# 2025_08_25_usb2spi.net
KiCad netlist of a schematic drawn in EasyEDA Pro
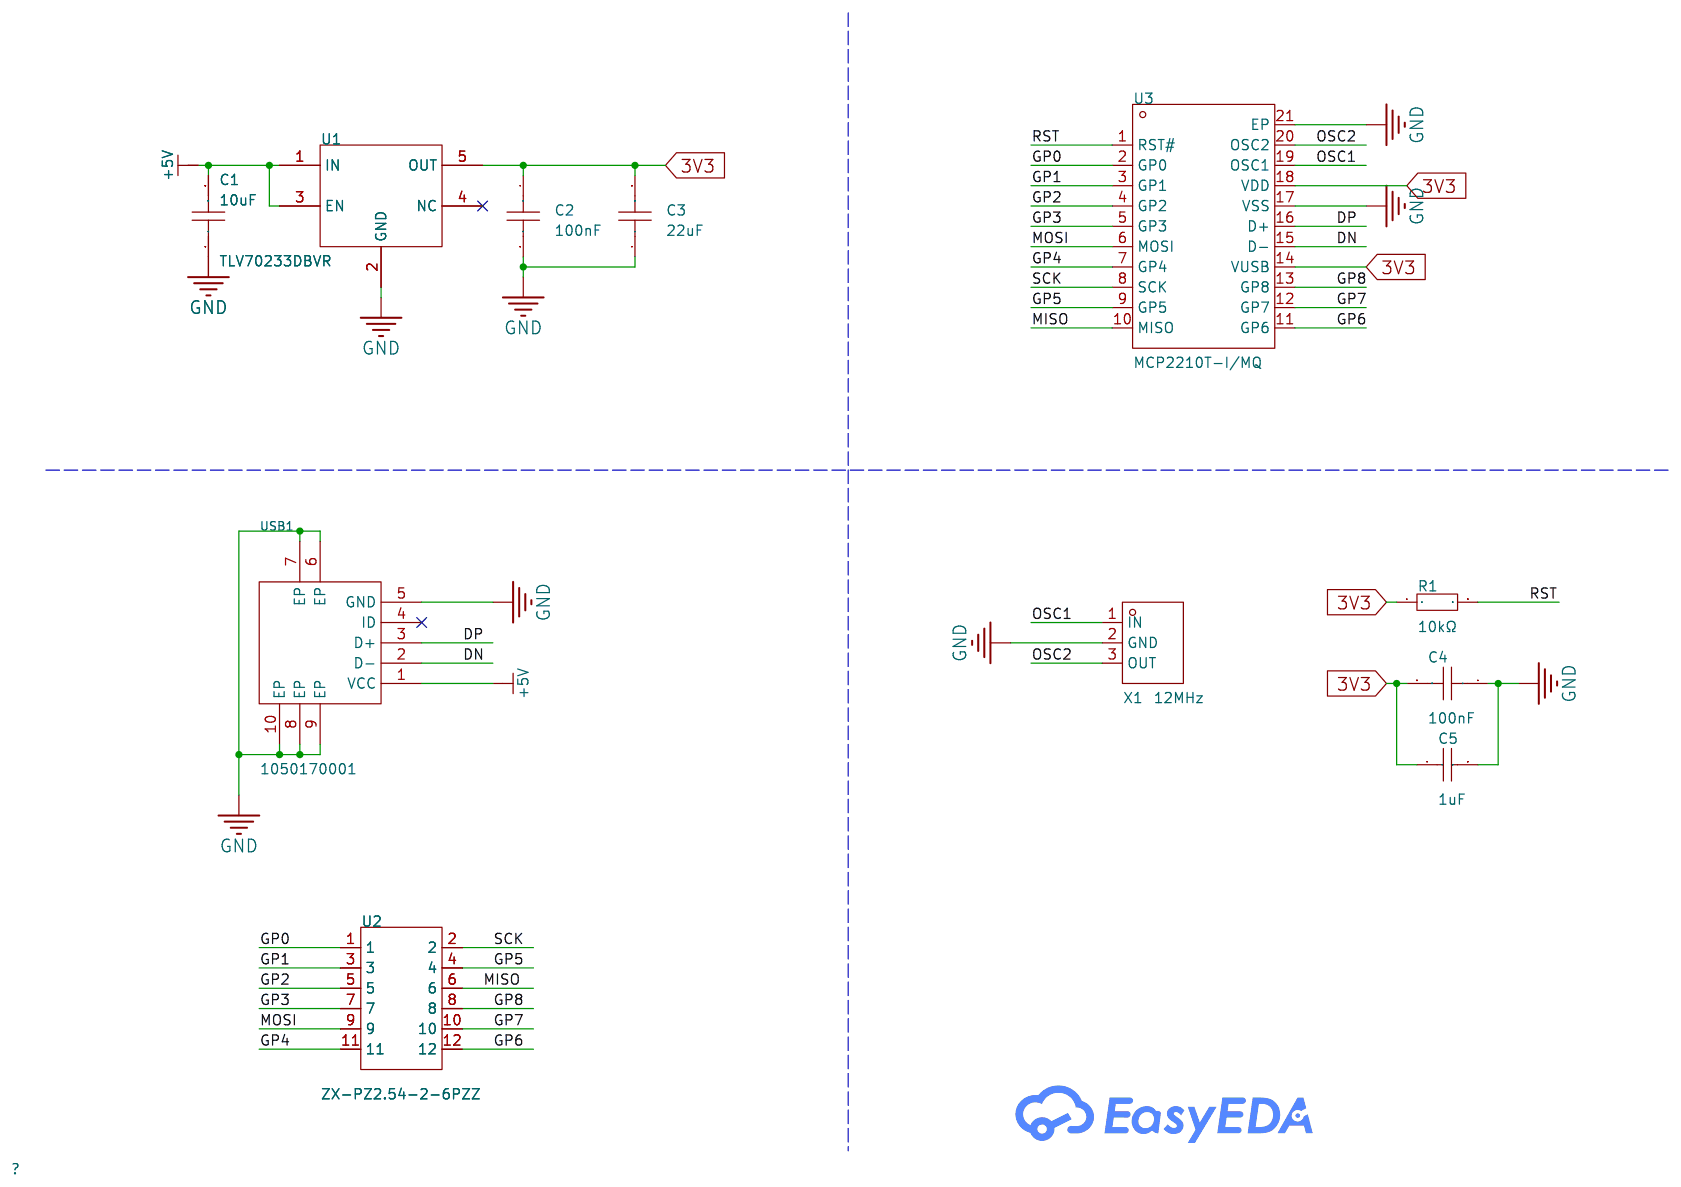
[diagram p0: schematic sheet]

(export (version "E")
  (design (tool "Eeschema 10.0.6"))
  (components
    (comp (ref "C1")
      (value "10uF")
      (footprint "easyedapro:C0402")
      (fields
        (field (name "Manufacturer Part") "CL05A106MP5NUNC")
        (field (name "Manufacturer") "SAMSUNG(三星)")
      )
      (libsource (lib "easyedapro") (part "CL05A106MP5NUNC_C315248"))
    )
    (comp (ref "C2")
      (value "100nF")
      (footprint "easyedapro:C0402")
      (fields
        (field (name "Manufacturer Part") "CL05B104KO5NNNC")
        (field (name "Manufacturer") "SAMSUNG(三星)")
      )
      (libsource (lib "easyedapro") (part "CL05B104KO5NNNC"))
    )
    (comp (ref "C3")
      (value "22uF")
      (footprint "easyedapro:C0402")
      (description "Capacitance:22uF Tolerance:±20% Tolerance:±20% Voltage Rating:6.3V Temperature Coefficient:X5R")
      (fields
        (field (name "Manufacturer Part") "GRM155R60J226ME11D")
        (field (name "Manufacturer") "muRata(村田)")
      )
      (libsource (lib "easyedapro") (part "GRM155R60J226ME11D"))
    )
    (comp (ref "C4")
      (value "100nF")
      (footprint "easyedapro:C0402")
      (fields
        (field (name "Manufacturer Part") "CL05B104KO5NNNC")
        (field (name "Manufacturer") "SAMSUNG(三星)")
      )
      (libsource (lib "easyedapro") (part "CL05B104KO5NNNC"))
    )
    (comp (ref "C5")
      (value "1uF")
      (footprint "easyedapro:C0402")
      (description "Capacitance:1uF Tolerance:±10% Tolerance:±10% Voltage Rating:10V Temperature Coefficient:X5R")
      (fields
        (field (name "Manufacturer Part") "CL05A105KP5NNNC")
        (field (name "Manufacturer") "SAMSUNG(三星)")
      )
      (libsource (lib "easyedapro") (part "CL05A105KP5NNNC"))
    )
    (comp (ref "R1")
      (value "10kΩ")
      (footprint "easyedapro:R0402")
      (fields (field (name "Manufacturer Part") "RC0402FR-0710KL") (field (name "Manufacturer") "YAGEO(国巨)"))
      (libsource (lib "easyedapro") (part "RC0402FR-0710KL"))
    )
    (comp (ref "U1")
      (value "TLV70233DBVR")
      (footprint "easyedapro:SOT-23-5_L3.0-W1.7-P0.95-LS2.8-BR")
      (fields (field (name "Manufacturer") "TI(德州仪器)"))
      (libsource (lib "easyedapro") (part "TLV70233DBVR"))
    )
    (comp (ref "U2")
      (value "ZX-PZ2.54-2-6PZZ")
      (footprint "easyedapro:HDR-TH_12P-P2.54-V-M-R2-C6-S2.54")
      (fields (field (name "Manufacturer") "Megastar(兆星)"))
      (libsource (lib "easyedapro") (part "ZX-PZ2.54-2-6PZZ"))
    )
    (comp (ref "U3")
      (value "MCP2210T-I/MQ")
      (footprint "easyedapro:QFN-20_L5.0-W5.0-P0.65-BL-EP3.3")
      (fields (field (name "Manufacturer") "MICROCHIP(美国微芯)"))
      (libsource (lib "easyedapro") (part "MCP2210T-I/MQ"))
    )
    (comp (ref "USB1")
      (value "1050170001")
      (footprint "easyedapro:MICRO-USB-SMD_105017-0001")
      (fields (field (name "Manufacturer") "MOLEX"))
      (libsource (lib "easyedapro") (part "105017-0001"))
    )
    (comp (ref "X1")
      (value "12MHz")
      (footprint "easyedapro:CRYSTAL-SMD_3P-L3.2-W1.3-P1.2-BL")
      (fields
        (field (name "Manufacturer Part") "CSTNE12M0G55A000R0")
        (field (name "Manufacturer") "muRata(村田)")
      )
      (libsource (lib "easyedapro") (part "CSTNE12M0G55A000R0"))
    )
  )
  (nets
    (net (code "1") (name "+5V") (class "Default")
      (node (ref "C1") (pin "2") (pinfunction "2_2") (pintype "unspecified"))
      (node (ref "U1") (pin "1") (pinfunction "IN_1") (pintype "unspecified"))
      (node (ref "U1") (pin "3") (pinfunction "EN_3") (pintype "unspecified"))
      (node (ref "USB1") (pin "1") (pinfunction "VCC_1") (pintype "input"))
    )
    (net (code "2") (name "/DN") (class "Default")
      (node (ref "U3") (pin "15") (pinfunction "D-_15") (pintype "unspecified"))
      (node (ref "USB1") (pin "2") (pinfunction "D-_2") (pintype "input"))
    )
    (net (code "3") (name "/DP") (class "Default")
      (node (ref "U3") (pin "16") (pinfunction "D+_16") (pintype "unspecified"))
      (node (ref "USB1") (pin "3") (pinfunction "D+_3") (pintype "input"))
    )
    (net (code "4") (name "/GP0") (class "Default")
      (node (ref "U2") (pin "1") (pinfunction "1_1") (pintype "unspecified"))
      (node (ref "U3") (pin "2") (pinfunction "GP0_2") (pintype "unspecified"))
    )
    (net (code "5") (name "/GP1") (class "Default")
      (node (ref "U2") (pin "3") (pinfunction "3_3") (pintype "unspecified"))
      (node (ref "U3") (pin "3") (pinfunction "GP1_3") (pintype "unspecified"))
    )
    (net (code "6") (name "/GP2") (class "Default")
      (node (ref "U2") (pin "5") (pinfunction "5_5") (pintype "unspecified"))
      (node (ref "U3") (pin "4") (pinfunction "GP2_4") (pintype "unspecified"))
    )
    (net (code "7") (name "/GP3") (class "Default")
      (node (ref "U2") (pin "7") (pinfunction "7_7") (pintype "unspecified"))
      (node (ref "U3") (pin "5") (pinfunction "GP3_5") (pintype "unspecified"))
    )
    (net (code "8") (name "/GP4") (class "Default")
      (node (ref "U2") (pin "11") (pinfunction "11_11") (pintype "unspecified"))
      (node (ref "U3") (pin "7") (pinfunction "GP4_7") (pintype "unspecified"))
    )
    (net (code "9") (name "/GP5") (class "Default")
      (node (ref "U2") (pin "4") (pinfunction "4_4") (pintype "unspecified"))
      (node (ref "U3") (pin "9") (pinfunction "GP5_9") (pintype "unspecified"))
    )
    (net (code "10") (name "/GP6") (class "Default")
      (node (ref "U2") (pin "12") (pinfunction "12_12") (pintype "unspecified"))
      (node (ref "U3") (pin "11") (pinfunction "GP6_11") (pintype "unspecified"))
    )
    (net (code "11") (name "/GP7") (class "Default")
      (node (ref "U2") (pin "10") (pinfunction "10_10") (pintype "unspecified"))
      (node (ref "U3") (pin "12") (pinfunction "GP7_12") (pintype "unspecified"))
    )
    (net (code "12") (name "/GP8") (class "Default")
      (node (ref "U2") (pin "8") (pinfunction "8_8") (pintype "unspecified"))
      (node (ref "U3") (pin "13") (pinfunction "GP8_13") (pintype "unspecified"))
    )
    (net (code "13") (name "/MISO") (class "Default")
      (node (ref "U2") (pin "6") (pinfunction "6_6") (pintype "unspecified"))
      (node (ref "U3") (pin "10") (pinfunction "MISO_10") (pintype "unspecified"))
    )
    (net (code "14") (name "/MOSI") (class "Default")
      (node (ref "U2") (pin "9") (pinfunction "9_9") (pintype "unspecified"))
      (node (ref "U3") (pin "6") (pinfunction "MOSI_6") (pintype "unspecified"))
    )
    (net (code "15") (name "/OSC1") (class "Default")
      (node (ref "U3") (pin "19") (pinfunction "OSC1_19") (pintype "unspecified"))
      (node (ref "X1") (pin "1") (pinfunction "IN_1") (pintype "unspecified"))
    )
    (net (code "16") (name "/OSC2") (class "Default")
      (node (ref "U3") (pin "20") (pinfunction "OSC2_20") (pintype "unspecified"))
      (node (ref "X1") (pin "3") (pinfunction "OUT_3") (pintype "unspecified"))
    )
    (net (code "17") (name "/RST") (class "Default")
      (node (ref "R1") (pin "2") (pinfunction "2_2") (pintype "input"))
      (node (ref "U3") (pin "1") (pinfunction "RST#_1") (pintype "unspecified"))
    )
    (net (code "18") (name "/SCK") (class "Default")
      (node (ref "U2") (pin "2") (pinfunction "2_2") (pintype "unspecified"))
      (node (ref "U3") (pin "8") (pinfunction "SCK_8") (pintype "unspecified"))
    )
    (net (code "19") (name "3V3") (class "Default")
      (node (ref "C2") (pin "1") (pinfunction "1_1") (pintype "unspecified"))
      (node (ref "C3") (pin "2") (pinfunction "2_2") (pintype "unspecified"))
      (node (ref "C4") (pin "2") (pinfunction "2_2") (pintype "unspecified"))
      (node (ref "C5") (pin "1") (pinfunction "1_1") (pintype "input"))
      (node (ref "R1") (pin "1") (pinfunction "1_1") (pintype "input"))
      (node (ref "U1") (pin "5") (pinfunction "OUT_5") (pintype "unspecified"))
      (node (ref "U3") (pin "14") (pinfunction "VUSB_14") (pintype "unspecified"))
      (node (ref "U3") (pin "18") (pinfunction "VDD_18") (pintype "unspecified"))
    )
    (net (code "20") (name "GND") (class "Default")
      (node (ref "C1") (pin "1") (pinfunction "1_1") (pintype "unspecified"))
      (node (ref "C2") (pin "2") (pinfunction "2_2") (pintype "unspecified"))
      (node (ref "C3") (pin "1") (pinfunction "1_1") (pintype "unspecified"))
      (node (ref "C4") (pin "1") (pinfunction "1_1") (pintype "unspecified"))
      (node (ref "C5") (pin "2") (pinfunction "2_2") (pintype "input"))
      (node (ref "U1") (pin "2") (pinfunction "GND_2") (pintype "unspecified"))
      (node (ref "U3") (pin "17") (pinfunction "VSS_17") (pintype "unspecified"))
      (node (ref "U3") (pin "21") (pinfunction "EP_21") (pintype "unspecified"))
      (node (ref "USB1") (pin "10") (pinfunction "EP_10") (pintype "input"))
      (node (ref "USB1") (pin "5") (pinfunction "GND_5") (pintype "input"))
      (node (ref "USB1") (pin "6") (pinfunction "EP_6") (pintype "input"))
      (node (ref "USB1") (pin "7") (pinfunction "EP_7") (pintype "input"))
      (node (ref "USB1") (pin "8") (pinfunction "EP_8") (pintype "input"))
      (node (ref "USB1") (pin "9") (pinfunction "EP_9") (pintype "input"))
      (node (ref "X1") (pin "2") (pinfunction "GND_2") (pintype "unspecified"))
    )
    (net (code "21") (name "unconnected-(U1-NC-Pad4)") (class "Default")
      (node (ref "U1") (pin "4") (pinfunction "NC_4") (pintype "unspecified+no_connect"))
    )
    (net (code "22") (name "unconnected-(USB1-ID-Pad4)") (class "Default")
      (node (ref "USB1") (pin "4") (pinfunction "ID_4") (pintype "input+no_connect"))
    )
  )
)
